# design.net
KiCad netlist of a schematic drawn in Altium Designer
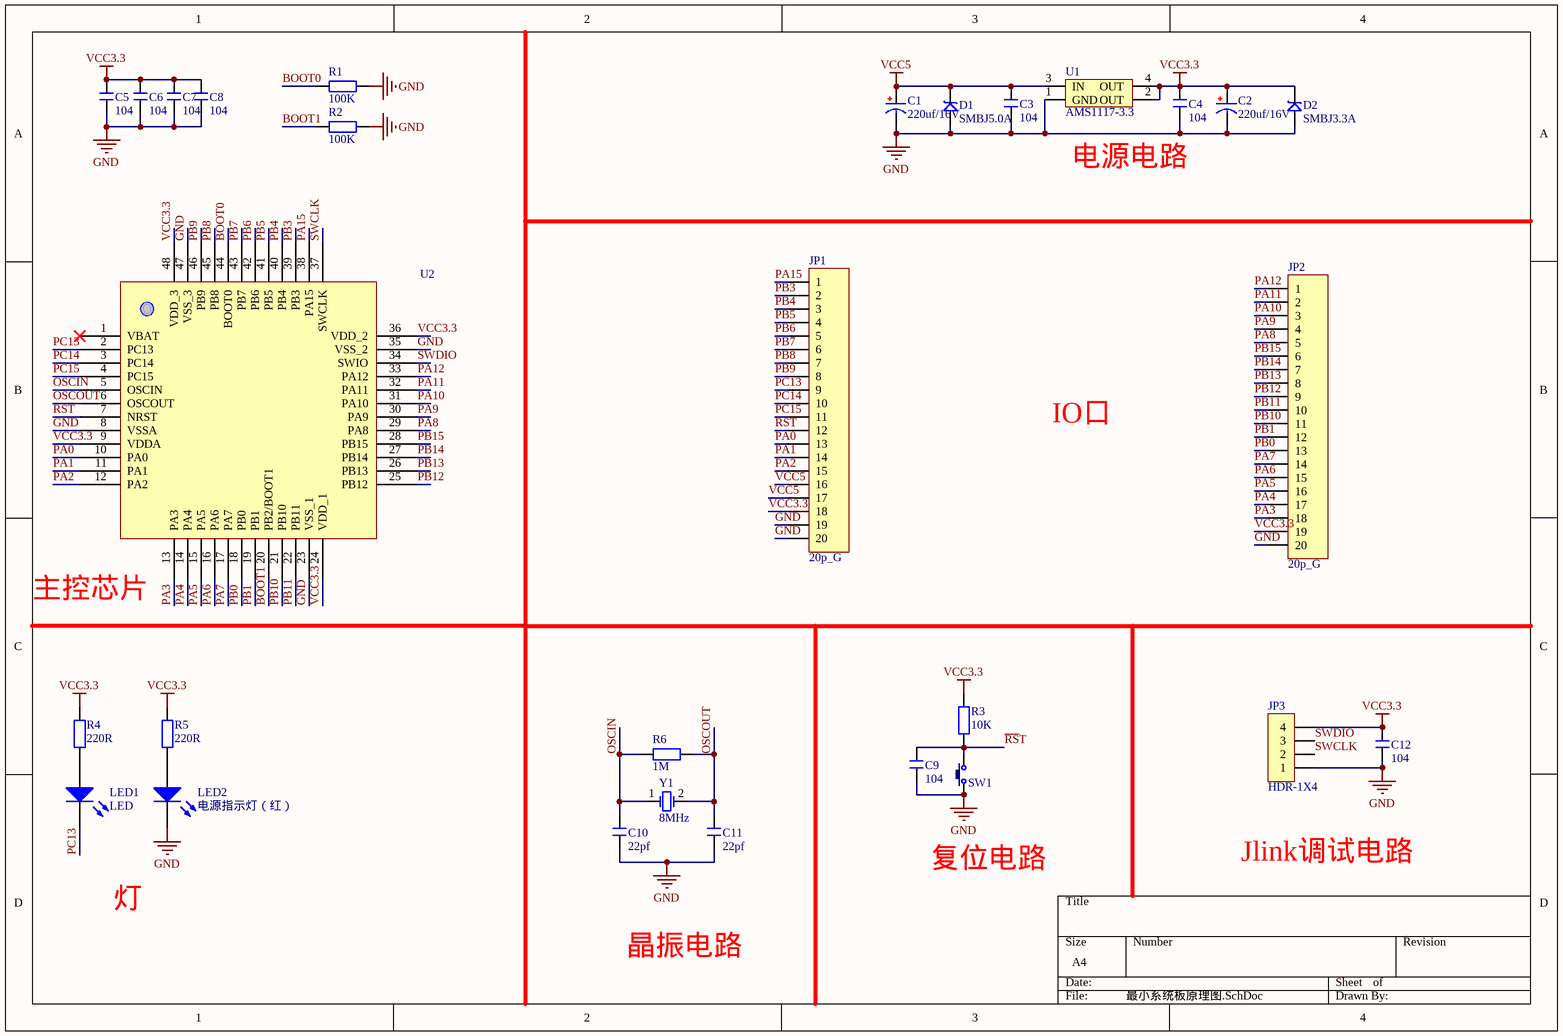
[diagram p0: 最小系统板原理图.SchDoc]

(export (version "E")
  (design (tool "Eeschema 10.0.6"))
  (components
    (comp (ref "C1")
      (value "220uf/16V")
      (footprint "CM D(6.3)")
      (description "极性电容")
      (libsource (lib "基础元件原理图库") (part "CAP"))
    )
    (comp (ref "C2")
      (value "220uf/16V")
      (footprint "CM D(6.3)")
      (description "极性电容")
      (libsource (lib "基础元件原理图库") (part "CAP"))
    )
    (comp (ref "C3")
      (value "104")
      (footprint "0603C")
      (description "贴片电容")
      (fields (field (name "Comment") "0603"))
      (libsource (lib "基础元件原理图库") (part "C"))
    )
    (comp (ref "C4")
      (value "104")
      (footprint "0603C")
      (description "贴片电容")
      (fields (field (name "Comment") "0603"))
      (libsource (lib "基础元件原理图库") (part "C"))
    )
    (comp (ref "C5")
      (value "104")
      (footprint "0603C")
      (description "贴片电容")
      (fields (field (name "Comment") "0603"))
      (libsource (lib "基础元件原理图库") (part "C"))
    )
    (comp (ref "C6")
      (value "104")
      (footprint "0603C")
      (description "贴片电容")
      (fields (field (name "Comment") "0603"))
      (libsource (lib "基础元件原理图库") (part "C"))
    )
    (comp (ref "C7")
      (value "104")
      (footprint "0603C")
      (description "贴片电容")
      (fields (field (name "Comment") "0603"))
      (libsource (lib "基础元件原理图库") (part "C"))
    )
    (comp (ref "C8")
      (value "104")
      (footprint "0603C")
      (description "贴片电容")
      (fields (field (name "Comment") "0603"))
      (libsource (lib "基础元件原理图库") (part "C"))
    )
    (comp (ref "C9")
      (value "104")
      (footprint "0603C")
      (description "贴片电容")
      (fields (field (name "Comment") "0603"))
      (libsource (lib "基础元件原理图库") (part "C"))
    )
    (comp (ref "C10")
      (value "22pf")
      (footprint "0603C")
      (description "贴片电容")
      (fields (field (name "Comment") "0603"))
      (libsource (lib "基础元件原理图库") (part "C"))
    )
    (comp (ref "C11")
      (value "22pf")
      (footprint "0603C")
      (description "贴片电容")
      (fields (field (name "Comment") "0603"))
      (libsource (lib "基础元件原理图库") (part "C"))
    )
    (comp (ref "C12")
      (value "104")
      (footprint "0603C")
      (description "贴片电容")
      (fields (field (name "Comment") "0603"))
      (libsource (lib "基础元件原理图库") (part "C"))
    )
    (comp (ref "D1")
      (value "SMBJ5.0A")
      (footprint "SMB")
      (description "TVS二极管")
      (libsource (lib "基础元件原理图库") (part "SMBJ"))
    )
    (comp (ref "D2")
      (value "SMBJ3.3A")
      (footprint "SMB")
      (description "TVS二极管")
      (libsource (lib "基础元件原理图库") (part "SMBJ"))
    )
    (comp (ref "JP1")
      (value "20p_G")
      (footprint "HDR-1X20")
      (description "20针排针")
      (libsource (lib "其他原理图库") (part "20p_G"))
    )
    (comp (ref "JP2")
      (value "20p_G")
      (footprint "HDR-1X20")
      (description "20针排针")
      (libsource (lib "其他原理图库") (part "20p_G"))
    )
    (comp (ref "JP3")
      (value "HDR-1X4")
      (footprint "HDR-1X4")
      (description "4针排针")
      (fields (field (name "版权归属") "源创客"))
      (libsource (lib "其他原理图库") (part "4p_G"))
    )
    (comp (ref "LED1")
      (value "LED")
      (footprint "LED 0603B")
      (description "RED 蓝、红")
      (fields (field (name "PUBLISHER") "Altium Limited"))
      (libsource (lib "基础元件原理图库") (part "LED"))
    )
    (comp (ref "LED2")
      (value "电源指示灯（红）")
      (footprint "LED 0603R")
      (description "RED 蓝、红")
      (fields (field (name "PUBLISHER") "Altium Limited"))
      (libsource (lib "基础元件原理图库") (part "LED"))
    )
    (comp (ref "R1")
      (value "100K")
      (footprint "0603R")
      (description "贴片电阻")
      (fields (field (name "Comment") "0603"))
      (libsource (lib "基础元件原理图库") (part "R"))
    )
    (comp (ref "R2")
      (value "100K")
      (footprint "0603R")
      (description "贴片电阻")
      (fields (field (name "Comment") "0603"))
      (libsource (lib "基础元件原理图库") (part "R"))
    )
    (comp (ref "R3")
      (value "10K")
      (footprint "0603R")
      (description "贴片电阻")
      (fields (field (name "Comment") "0603"))
      (libsource (lib "基础元件原理图库") (part "R"))
    )
    (comp (ref "R4")
      (value "220R")
      (footprint "0603R")
      (description "贴片电阻")
      (fields (field (name "Comment") "0603"))
      (libsource (lib "基础元件原理图库") (part "R"))
    )
    (comp (ref "R5")
      (value "220R")
      (footprint "0603R")
      (description "贴片电阻")
      (fields (field (name "Comment") "0603"))
      (libsource (lib "基础元件原理图库") (part "R"))
    )
    (comp (ref "R6")
      (value "1M")
      (footprint "0603R")
      (description "贴片电阻")
      (fields (field (name "Comment") "0603"))
      (libsource (lib "基础元件原理图库") (part "R"))
    )
    (comp (ref "SW1")
      (value "TSW")
      (footprint "TSW SMD-3*6*2.5")
      (description "轻触开关")
      (fields (field (name "版权归属") "源创客"))
      (libsource (lib "其他原理图库") (part "TSW"))
    )
    (comp (ref "U1")
      (value "AMS1117-3.3")
      (footprint "SOT-223")
      (description "LDO5-3.3稳压芯片")
      (libsource (lib "芯片原理图库") (part "AMS1117"))
    )
    (comp (ref "U2")
      (value "STM32F103C8T6")
      (footprint "LQFP-48")
      (description "MCU")
      (libsource (lib "芯片原理图库") (part "STM32F103C8T6"))
    )
    (comp (ref "Y1")
      (value "8MHz")
      (footprint "OSC HC-49S")
      (description "晶振")
      (fields (field (name "PUBLISHER") "Altium Limited"))
      (libsource (lib "其他原理图库") (part "XTAL"))
    )
  )
  (nets
    (net (code "1") (name "/BOOT0") (class "Default")
      (node (ref "R1") (pin "2") (pinfunction "2_2") (pintype "passive"))
      (node (ref "U2") (pin "44") (pinfunction "BOOT0_44") (pintype "passive"))
    )
    (net (code "2") (name "/BOOT1") (class "Default")
      (node (ref "R2") (pin "2") (pinfunction "2_2") (pintype "passive"))
      (node (ref "U2") (pin "20") (pinfunction "PB2/BOOT1_20") (pintype "passive"))
    )
    (net (code "3") (name "/OSCIN") (class "Default")
      (node (ref "C10") (pin "2") (pinfunction "2_2") (pintype "passive"))
      (node (ref "R6") (pin "1") (pinfunction "1_1") (pintype "passive"))
      (node (ref "U2") (pin "5") (pinfunction "OSCIN_5") (pintype "passive"))
      (node (ref "Y1") (pin "1") (pinfunction "OSC1_1") (pintype "passive"))
    )
    (net (code "4") (name "/OSCOUT") (class "Default")
      (node (ref "C11") (pin "2") (pinfunction "2_2") (pintype "passive"))
      (node (ref "R6") (pin "2") (pinfunction "2_2") (pintype "passive"))
      (node (ref "U2") (pin "6") (pinfunction "OSCOUT_6") (pintype "passive"))
      (node (ref "Y1") (pin "2") (pinfunction "OSC2_2") (pintype "passive"))
    )
    (net (code "5") (name "/PA0") (class "Default")
      (node (ref "JP1") (pin "13") (pinfunction "13_13") (pintype "passive"))
      (node (ref "U2") (pin "10") (pinfunction "PA0_10") (pintype "passive"))
    )
    (net (code "6") (name "/PA1") (class "Default")
      (node (ref "JP1") (pin "14") (pinfunction "14_14") (pintype "passive"))
      (node (ref "U2") (pin "11") (pinfunction "PA1_11") (pintype "passive"))
    )
    (net (code "7") (name "/PA2") (class "Default")
      (node (ref "JP1") (pin "15") (pinfunction "15_15") (pintype "passive"))
      (node (ref "U2") (pin "12") (pinfunction "PA2_12") (pintype "passive"))
    )
    (net (code "8") (name "/PA3") (class "Default")
      (node (ref "JP2") (pin "18") (pinfunction "18_18") (pintype "passive"))
      (node (ref "U2") (pin "13") (pinfunction "PA3_13") (pintype "passive"))
    )
    (net (code "9") (name "/PA4") (class "Default")
      (node (ref "JP2") (pin "17") (pinfunction "17_17") (pintype "passive"))
      (node (ref "U2") (pin "14") (pinfunction "PA4_14") (pintype "passive"))
    )
    (net (code "10") (name "/PA5") (class "Default")
      (node (ref "JP2") (pin "16") (pinfunction "16_16") (pintype "passive"))
      (node (ref "U2") (pin "15") (pinfunction "PA5_15") (pintype "passive"))
    )
    (net (code "11") (name "/PA6") (class "Default")
      (node (ref "JP2") (pin "15") (pinfunction "15_15") (pintype "passive"))
      (node (ref "U2") (pin "16") (pinfunction "PA6_16") (pintype "passive"))
    )
    (net (code "12") (name "/PA7") (class "Default")
      (node (ref "JP2") (pin "14") (pinfunction "14_14") (pintype "passive"))
      (node (ref "U2") (pin "17") (pinfunction "PA7_17") (pintype "passive"))
    )
    (net (code "13") (name "/PA8") (class "Default")
      (node (ref "JP2") (pin "5") (pinfunction "5_5") (pintype "passive"))
      (node (ref "U2") (pin "29") (pinfunction "PA8_29") (pintype "passive"))
    )
    (net (code "14") (name "/PA9") (class "Default")
      (node (ref "JP2") (pin "4") (pinfunction "4_4") (pintype "passive"))
      (node (ref "U2") (pin "30") (pinfunction "PA9_30") (pintype "passive"))
    )
    (net (code "15") (name "/PA10") (class "Default")
      (node (ref "JP2") (pin "3") (pinfunction "3_3") (pintype "passive"))
      (node (ref "U2") (pin "31") (pinfunction "PA10_31") (pintype "passive"))
    )
    (net (code "16") (name "/PA11") (class "Default")
      (node (ref "JP2") (pin "2") (pinfunction "2_2") (pintype "passive"))
      (node (ref "U2") (pin "32") (pinfunction "PA11_32") (pintype "passive"))
    )
    (net (code "17") (name "/PA12") (class "Default")
      (node (ref "JP2") (pin "1") (pinfunction "1_1") (pintype "passive"))
      (node (ref "U2") (pin "33") (pinfunction "PA12_33") (pintype "passive"))
    )
    (net (code "18") (name "/PA15") (class "Default")
      (node (ref "JP1") (pin "1") (pinfunction "1_1") (pintype "passive"))
      (node (ref "U2") (pin "38") (pinfunction "PA15_38") (pintype "passive"))
    )
    (net (code "19") (name "/PB0") (class "Default")
      (node (ref "JP2") (pin "13") (pinfunction "13_13") (pintype "passive"))
      (node (ref "U2") (pin "18") (pinfunction "PB0_18") (pintype "passive"))
    )
    (net (code "20") (name "/PB1") (class "Default")
      (node (ref "JP2") (pin "12") (pinfunction "12_12") (pintype "passive"))
      (node (ref "U2") (pin "19") (pinfunction "PB1_19") (pintype "passive"))
    )
    (net (code "21") (name "/PB3") (class "Default")
      (node (ref "JP1") (pin "2") (pinfunction "2_2") (pintype "passive"))
      (node (ref "U2") (pin "39") (pinfunction "PB3_39") (pintype "passive"))
    )
    (net (code "22") (name "/PB4") (class "Default")
      (node (ref "JP1") (pin "3") (pinfunction "3_3") (pintype "passive"))
      (node (ref "U2") (pin "40") (pinfunction "PB4_40") (pintype "passive"))
    )
    (net (code "23") (name "/PB5") (class "Default")
      (node (ref "JP1") (pin "4") (pinfunction "4_4") (pintype "passive"))
      (node (ref "U2") (pin "41") (pinfunction "PB5_41") (pintype "passive"))
    )
    (net (code "24") (name "/PB6") (class "Default")
      (node (ref "JP1") (pin "5") (pinfunction "5_5") (pintype "passive"))
      (node (ref "U2") (pin "42") (pinfunction "PB6_42") (pintype "passive"))
    )
    (net (code "25") (name "/PB7") (class "Default")
      (node (ref "JP1") (pin "6") (pinfunction "6_6") (pintype "passive"))
      (node (ref "U2") (pin "43") (pinfunction "PB7_43") (pintype "passive"))
    )
    (net (code "26") (name "/PB8") (class "Default")
      (node (ref "JP1") (pin "7") (pinfunction "7_7") (pintype "passive"))
      (node (ref "U2") (pin "45") (pinfunction "PB8_45") (pintype "passive"))
    )
    (net (code "27") (name "/PB9") (class "Default")
      (node (ref "JP1") (pin "8") (pinfunction "8_8") (pintype "passive"))
      (node (ref "U2") (pin "46") (pinfunction "PB9_46") (pintype "passive"))
    )
    (net (code "28") (name "/PB10") (class "Default")
      (node (ref "JP2") (pin "11") (pinfunction "11_11") (pintype "passive"))
      (node (ref "U2") (pin "21") (pinfunction "PB10_21") (pintype "passive"))
    )
    (net (code "29") (name "/PB11") (class "Default")
      (node (ref "JP2") (pin "10") (pinfunction "10_10") (pintype "passive"))
      (node (ref "U2") (pin "22") (pinfunction "PB11_22") (pintype "passive"))
    )
    (net (code "30") (name "/PB12") (class "Default")
      (node (ref "JP2") (pin "9") (pinfunction "9_9") (pintype "passive"))
      (node (ref "U2") (pin "25") (pinfunction "PB12_25") (pintype "passive"))
    )
    (net (code "31") (name "/PB13") (class "Default")
      (node (ref "JP2") (pin "8") (pinfunction "8_8") (pintype "passive"))
      (node (ref "U2") (pin "26") (pinfunction "PB13_26") (pintype "passive"))
    )
    (net (code "32") (name "/PB14") (class "Default")
      (node (ref "JP2") (pin "7") (pinfunction "7_7") (pintype "passive"))
      (node (ref "U2") (pin "27") (pinfunction "PB14_27") (pintype "passive"))
    )
    (net (code "33") (name "/PB15") (class "Default")
      (node (ref "JP2") (pin "6") (pinfunction "6_6") (pintype "passive"))
      (node (ref "U2") (pin "28") (pinfunction "PB15_28") (pintype "passive"))
    )
    (net (code "34") (name "/PC13") (class "Default")
      (node (ref "JP1") (pin "9") (pinfunction "9_9") (pintype "passive"))
      (node (ref "LED1") (pin "2") (pinfunction "K_2") (pintype "passive"))
      (node (ref "U2") (pin "2") (pinfunction "PC13_2") (pintype "passive"))
    )
    (net (code "35") (name "/PC14") (class "Default")
      (node (ref "JP1") (pin "10") (pinfunction "10_10") (pintype "passive"))
      (node (ref "U2") (pin "3") (pinfunction "PC14_3") (pintype "passive"))
    )
    (net (code "36") (name "/PC15") (class "Default")
      (node (ref "JP1") (pin "11") (pinfunction "11_11") (pintype "passive"))
      (node (ref "U2") (pin "4") (pinfunction "PC15_4") (pintype "passive"))
    )
    (net (code "37") (name "/SWCLK") (class "Default")
      (node (ref "JP3") (pin "2") (pinfunction "2_2") (pintype "passive"))
      (node (ref "U2") (pin "37") (pinfunction "SWCLK_37") (pintype "passive"))
    )
    (net (code "38") (name "/SWDIO") (class "Default")
      (node (ref "JP3") (pin "3") (pinfunction "3_3") (pintype "passive"))
      (node (ref "U2") (pin "34") (pinfunction "SWIO_34") (pintype "passive"))
    )
    (net (code "39") (name "/~{RS}T") (class "Default")
      (node (ref "C9") (pin "2") (pinfunction "2_2") (pintype "passive"))
      (node (ref "JP1") (pin "12") (pinfunction "12_12") (pintype "passive"))
      (node (ref "R3") (pin "1") (pinfunction "1_1") (pintype "passive"))
      (node (ref "SW1") (pin "2") (pinfunction "2_2") (pintype "passive"))
      (node (ref "U2") (pin "7") (pinfunction "NRST_7") (pintype "passive"))
    )
    (net (code "40") (name "GND") (class "Default")
      (node (ref "C1") (pin "2") (pinfunction "GND_2") (pintype "passive"))
      (node (ref "C10") (pin "1") (pinfunction "1_1") (pintype "passive"))
      (node (ref "C11") (pin "1") (pinfunction "1_1") (pintype "passive"))
      (node (ref "C12") (pin "1") (pinfunction "1_1") (pintype "passive"))
      (node (ref "C2") (pin "2") (pinfunction "GND_2") (pintype "passive"))
      (node (ref "C3") (pin "1") (pinfunction "1_1") (pintype "passive"))
      (node (ref "C4") (pin "1") (pinfunction "1_1") (pintype "passive"))
      (node (ref "C5") (pin "1") (pinfunction "1_1") (pintype "passive"))
      (node (ref "C6") (pin "1") (pinfunction "1_1") (pintype "passive"))
      (node (ref "C7") (pin "1") (pinfunction "1_1") (pintype "passive"))
      (node (ref "C8") (pin "1") (pinfunction "1_1") (pintype "passive"))
      (node (ref "C9") (pin "1") (pinfunction "1_1") (pintype "passive"))
      (node (ref "D1") (pin "1") (pintype "passive"))
      (node (ref "D2") (pin "1") (pintype "passive"))
      (node (ref "JP1") (pin "19") (pinfunction "19_19") (pintype "passive"))
      (node (ref "JP1") (pin "20") (pinfunction "20_20") (pintype "passive"))
      (node (ref "JP2") (pin "20") (pinfunction "20_20") (pintype "passive"))
      (node (ref "JP3") (pin "1") (pinfunction "1_1") (pintype "passive"))
      (node (ref "LED2") (pin "2") (pinfunction "K_2") (pintype "passive"))
      (node (ref "R1") (pin "1") (pinfunction "1_1") (pintype "passive"))
      (node (ref "R2") (pin "1") (pinfunction "1_1") (pintype "passive"))
      (node (ref "SW1") (pin "1") (pinfunction "1_1") (pintype "passive"))
      (node (ref "U1") (pin "1") (pinfunction "GND_1") (pintype "passive"))
      (node (ref "U2") (pin "23") (pinfunction "VSS_1_23") (pintype "passive"))
      (node (ref "U2") (pin "35") (pinfunction "VSS_2_35") (pintype "passive"))
      (node (ref "U2") (pin "47") (pinfunction "VSS_3_47") (pintype "passive"))
      (node (ref "U2") (pin "8") (pinfunction "VSSA_8") (pintype "passive"))
    )
    (net (code "41") (name "Net-(LED1-A)") (class "Default")
      (node (ref "LED1") (pin "1") (pinfunction "A_1") (pintype "passive"))
      (node (ref "R4") (pin "2") (pinfunction "2_2") (pintype "passive"))
    )
    (net (code "42") (name "Net-(LED2-A)") (class "Default")
      (node (ref "LED2") (pin "1") (pinfunction "A_1") (pintype "passive"))
      (node (ref "R5") (pin "2") (pinfunction "2_2") (pintype "passive"))
    )
    (net (code "43") (name "VCC3.3") (class "Default")
      (node (ref "C12") (pin "2") (pinfunction "2_2") (pintype "passive"))
      (node (ref "C2") (pin "1") (pinfunction "VCC_1") (pintype "passive"))
      (node (ref "C4") (pin "2") (pinfunction "2_2") (pintype "passive"))
      (node (ref "C5") (pin "2") (pinfunction "2_2") (pintype "passive"))
      (node (ref "C6") (pin "2") (pinfunction "2_2") (pintype "passive"))
      (node (ref "C7") (pin "2") (pinfunction "2_2") (pintype "passive"))
      (node (ref "C8") (pin "2") (pinfunction "2_2") (pintype "passive"))
      (node (ref "D2") (pin "2") (pintype "passive"))
      (node (ref "JP1") (pin "18") (pinfunction "18_18") (pintype "passive"))
      (node (ref "JP2") (pin "19") (pinfunction "19_19") (pintype "passive"))
      (node (ref "JP3") (pin "4") (pinfunction "4_4") (pintype "passive"))
      (node (ref "R3") (pin "2") (pinfunction "2_2") (pintype "passive"))
      (node (ref "R4") (pin "1") (pinfunction "1_1") (pintype "passive"))
      (node (ref "R5") (pin "1") (pinfunction "1_1") (pintype "passive"))
      (node (ref "U1") (pin "2") (pinfunction "OUT_2") (pintype "passive"))
      (node (ref "U1") (pin "4") (pinfunction "OUT_4") (pintype "passive"))
      (node (ref "U2") (pin "24") (pinfunction "VDD_1_24") (pintype "passive"))
      (node (ref "U2") (pin "36") (pinfunction "VDD_2_36") (pintype "passive"))
      (node (ref "U2") (pin "48") (pinfunction "VDD_3_48") (pintype "passive"))
      (node (ref "U2") (pin "9") (pinfunction "VDDA_9") (pintype "passive"))
    )
    (net (code "44") (name "VCC5") (class "Default")
      (node (ref "C1") (pin "1") (pinfunction "VCC_1") (pintype "passive"))
      (node (ref "C3") (pin "2") (pinfunction "2_2") (pintype "passive"))
      (node (ref "D1") (pin "2") (pintype "passive"))
      (node (ref "JP1") (pin "16") (pinfunction "16_16") (pintype "passive"))
      (node (ref "JP1") (pin "17") (pinfunction "17_17") (pintype "passive"))
      (node (ref "U1") (pin "3") (pinfunction "IN_3") (pintype "passive"))
    )
    (net (code "45") (name "unconnected-(U2-VBAT-Pad1)") (class "Default")
      (node (ref "U2") (pin "1") (pinfunction "VBAT_1") (pintype "passive+no_connect"))
    )
  )
)
